# ESPIR.net
KiCad netlist of a schematic drawn in EAGLE
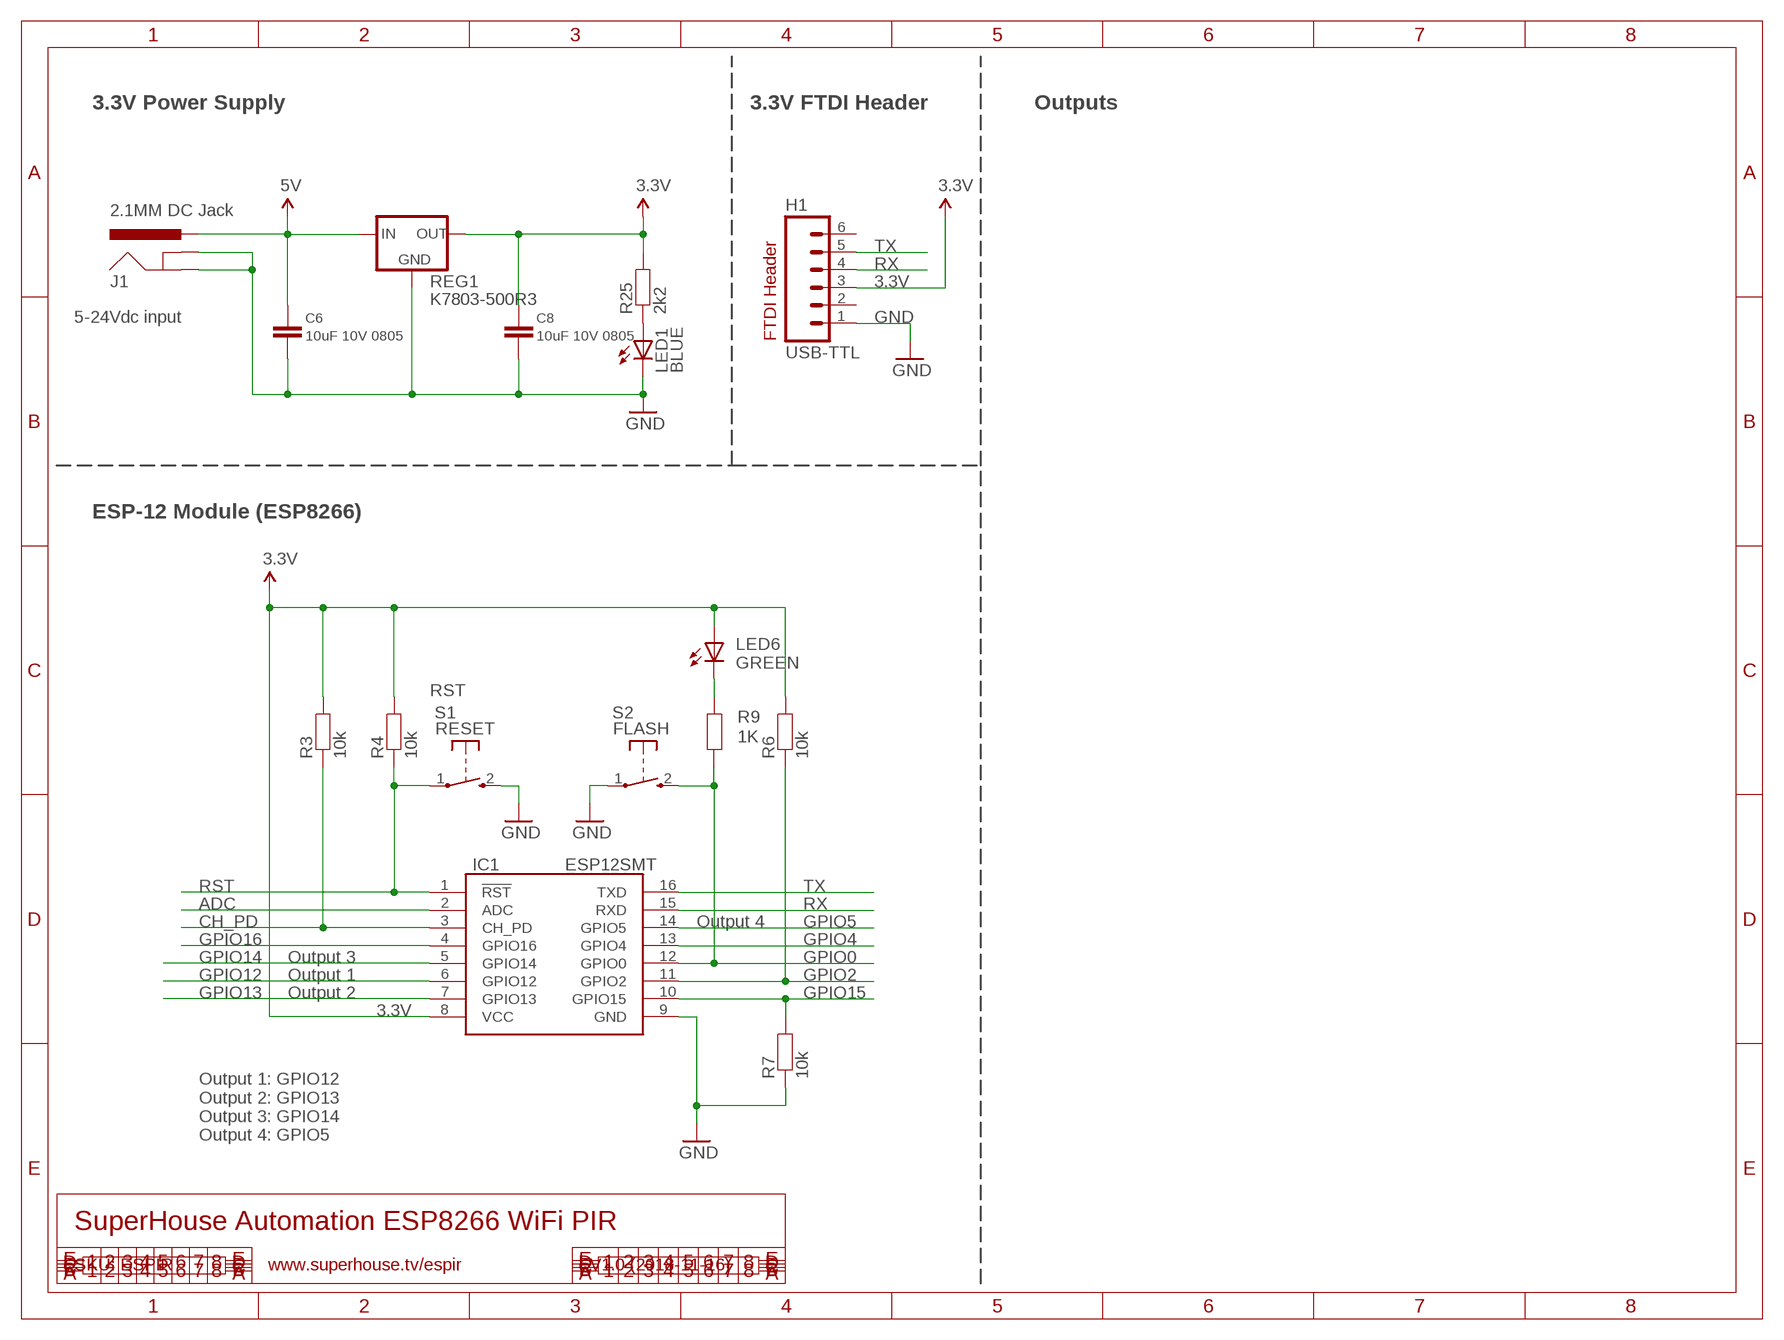
[diagram p0: schematic, sheet 1]

(export (version "E")
  (design (tool "Eeschema 10.0.6"))
  (components
    (comp (ref "C6")
      (value "10uF 10V 0805")
      (footprint "eagle-import:C0805")
      (libsource (lib "eagle-import") (part "C-EUC0805"))
    )
    (comp (ref "C8")
      (value "10uF 10V 0805")
      (footprint "eagle-import:C0805")
      (libsource (lib "eagle-import") (part "C-EUC0805"))
    )
    (comp (ref "H1")
      (value "USB-TTL")
      (footprint "eagle-import:1X06")
      (libsource (lib "eagle-import") (part "M06SIP"))
    )
    (comp (ref "IC1")
      (value "ESP12SMT")
      (footprint "eagle-import:ESP12")
      (libsource (lib "eagle-import") (part "ESP12SMT"))
    )
    (comp (ref "J1")
      (value "2.1MM DC Jack")
      (footprint "eagle-import:POWER_JACK_PTH_SLOTS")
      (libsource (lib "eagle-import") (part "POWER_JACKPTH_SLOTS"))
    )
    (comp (ref "LED1")
      (value "BLUE")
      (footprint "eagle-import:LED-0603")
      (libsource (lib "eagle-import") (part "LED0603"))
    )
    (comp (ref "LED6")
      (value "GREEN")
      (footprint "eagle-import:LED-0603")
      (libsource (lib "eagle-import") (part "freetronics-master-v1_LED0603"))
    )
    (comp (ref "R3")
      (value "10k")
      (footprint "eagle-import:0603")
      (libsource (lib "eagle-import") (part "RESISTOR0603"))
    )
    (comp (ref "R4")
      (value "10k")
      (footprint "eagle-import:0603")
      (libsource (lib "eagle-import") (part "RESISTOR0603"))
    )
    (comp (ref "R6")
      (value "10k")
      (footprint "eagle-import:0603")
      (libsource (lib "eagle-import") (part "RESISTOR0603"))
    )
    (comp (ref "R7")
      (value "10k")
      (footprint "eagle-import:0603")
      (libsource (lib "eagle-import") (part "RESISTOR0603"))
    )
    (comp (ref "R9")
      (value "1K")
      (footprint "eagle-import:0603")
      (libsource (lib "eagle-import") (part "freetronics-master-v1_RESISTOR0603"))
    )
    (comp (ref "R25")
      (value "2k2")
      (footprint "eagle-import:0603")
      (libsource (lib "eagle-import") (part "RESISTOR0603"))
    )
    (comp (ref "REG1")
      (value "K7803-500R3")
      (footprint "eagle-import:K78XX-500R3")
      (libsource (lib "eagle-import") (part "K78XX-500R3"))
    )
    (comp (ref "S1")
      (value "RESET")
      (footprint "eagle-import:TACTILE_SWITCH_SMD_2PIN_TINY")
      (libsource (lib "eagle-import") (part "TAC_SWITCH_2PINSMT"))
    )
    (comp (ref "S2")
      (value "FLASH")
      (footprint "eagle-import:TACTILE_SWITCH_SMD_2PIN_TINY")
      (libsource (lib "eagle-import") (part "TAC_SWITCH_2PINSMT"))
    )
  )
  (nets
    (net (code "1") (name "/ADC") (class "Default")
      (node (ref "IC1") (pin "2") (pinfunction "ADC_2") (pintype "input"))
    )
    (net (code "2") (name "/CH_PD") (class "Default")
      (node (ref "IC1") (pin "3") (pinfunction "CH_PD_3") (pintype "input"))
      (node (ref "R3") (pin "1") (pinfunction "1_1") (pintype "passive"))
    )
    (net (code "3") (name "/GPIO0") (class "Default")
      (node (ref "IC1") (pin "12") (pinfunction "GPIO0_12") (pintype "bidirectional"))
      (node (ref "R9") (pin "2") (pinfunction "2_2") (pintype "passive"))
      (node (ref "S2") (pin "2") (pinfunction "S_2") (pintype "passive"))
    )
    (net (code "4") (name "/GPIO2") (class "Default")
      (node (ref "IC1") (pin "11") (pinfunction "GPIO2_11") (pintype "bidirectional"))
      (node (ref "R6") (pin "1") (pinfunction "1_1") (pintype "passive"))
    )
    (net (code "5") (name "/GPIO4") (class "Default")
      (node (ref "IC1") (pin "13") (pinfunction "GPIO4_13") (pintype "bidirectional"))
    )
    (net (code "6") (name "/GPIO5") (class "Default")
      (node (ref "IC1") (pin "14") (pinfunction "GPIO5_14") (pintype "bidirectional"))
    )
    (net (code "7") (name "/GPIO12") (class "Default")
      (node (ref "IC1") (pin "6") (pinfunction "GPIO12_6") (pintype "bidirectional"))
    )
    (net (code "8") (name "/GPIO13") (class "Default")
      (node (ref "IC1") (pin "7") (pinfunction "GPIO13_7") (pintype "bidirectional"))
    )
    (net (code "9") (name "/GPIO14") (class "Default")
      (node (ref "IC1") (pin "5") (pinfunction "GPIO14_5") (pintype "bidirectional"))
    )
    (net (code "10") (name "/GPIO15") (class "Default")
      (node (ref "IC1") (pin "10") (pinfunction "GPIO15_10") (pintype "bidirectional"))
      (node (ref "R7") (pin "2") (pinfunction "2_2") (pintype "passive"))
    )
    (net (code "11") (name "/GPIO16") (class "Default")
      (node (ref "IC1") (pin "4") (pinfunction "GPIO16_4") (pintype "bidirectional"))
    )
    (net (code "12") (name "/RST") (class "Default")
      (node (ref "IC1") (pin "1") (pinfunction "~{RST}_1") (pintype "bidirectional"))
      (node (ref "R4") (pin "1") (pinfunction "1_1") (pintype "passive"))
      (node (ref "S1") (pin "1") (pinfunction "P_1") (pintype "passive"))
    )
    (net (code "13") (name "/RX") (class "Default")
      (node (ref "H1") (pin "4") (pinfunction "4_4") (pintype "passive"))
      (node (ref "IC1") (pin "15") (pinfunction "RXD_15") (pintype "input"))
    )
    (net (code "14") (name "/TX") (class "Default")
      (node (ref "H1") (pin "5") (pinfunction "5_5") (pintype "passive"))
      (node (ref "IC1") (pin "16") (pinfunction "TXD_16") (pintype "output"))
    )
    (net (code "15") (name "3.3V") (class "Default")
      (node (ref "C8") (pin "1") (pinfunction "1_1") (pintype "passive"))
      (node (ref "H1") (pin "3") (pinfunction "3_3") (pintype "passive"))
      (node (ref "IC1") (pin "8") (pinfunction "VCC_8") (pintype "power_in"))
      (node (ref "LED6") (pin "A") (pinfunction "A_A") (pintype "passive"))
      (node (ref "R25") (pin "2") (pinfunction "2_2") (pintype "passive"))
      (node (ref "R3") (pin "2") (pinfunction "2_2") (pintype "passive"))
      (node (ref "R4") (pin "2") (pinfunction "2_2") (pintype "passive"))
      (node (ref "R6") (pin "2") (pinfunction "2_2") (pintype "passive"))
      (node (ref "REG1") (pin "3") (pinfunction "OUT_3") (pintype "output"))
    )
    (net (code "16") (name "5V") (class "Default")
      (node (ref "C6") (pin "1") (pinfunction "1_1") (pintype "passive"))
      (node (ref "J1") (pin "PWR") (pinfunction "PWR_PWR") (pintype "bidirectional"))
      (node (ref "REG1") (pin "1") (pinfunction "IN_1") (pintype "input"))
    )
    (net (code "17") (name "GND") (class "Default")
      (node (ref "C6") (pin "2") (pinfunction "2_2") (pintype "passive"))
      (node (ref "C8") (pin "2") (pinfunction "2_2") (pintype "passive"))
      (node (ref "H1") (pin "1") (pinfunction "1_1") (pintype "passive"))
      (node (ref "IC1") (pin "9") (pinfunction "GND_9") (pintype "power_in"))
      (node (ref "J1") (pin "GND") (pinfunction "GND_GND") (pintype "bidirectional"))
      (node (ref "J1") (pin "GNDBREAK") (pinfunction "GNDBREAK_GNDBREAK") (pintype "bidirectional"))
      (node (ref "LED1") (pin "C") (pinfunction "C_C") (pintype "passive"))
      (node (ref "R7") (pin "1") (pinfunction "1_1") (pintype "passive"))
      (node (ref "REG1") (pin "2") (pinfunction "GND_2") (pintype "input"))
      (node (ref "S1") (pin "2") (pinfunction "S_2") (pintype "passive"))
      (node (ref "S2") (pin "1") (pinfunction "P_1") (pintype "passive"))
    )
    (net (code "18") (name "Net-(LED1-PadA)") (class "Default")
      (node (ref "LED1") (pin "A") (pinfunction "A_A") (pintype "passive"))
      (node (ref "R25") (pin "1") (pinfunction "1_1") (pintype "passive"))
    )
    (net (code "19") (name "Net-(LED6-PadC)") (class "Default")
      (node (ref "LED6") (pin "C") (pinfunction "C_C") (pintype "passive"))
      (node (ref "R9") (pin "1") (pinfunction "1_1") (pintype "passive"))
    )
    (net (code "20") (name "unconnected-(H1-Pad2)") (class "Default")
      (node (ref "H1") (pin "2") (pinfunction "2_2") (pintype "passive"))
    )
    (net (code "21") (name "unconnected-(H1-Pad6)") (class "Default")
      (node (ref "H1") (pin "6") (pinfunction "6_6") (pintype "passive"))
    )
  )
)
